# jack10_breakout.net
KiCad netlist of a schematic drawn in EAGLE
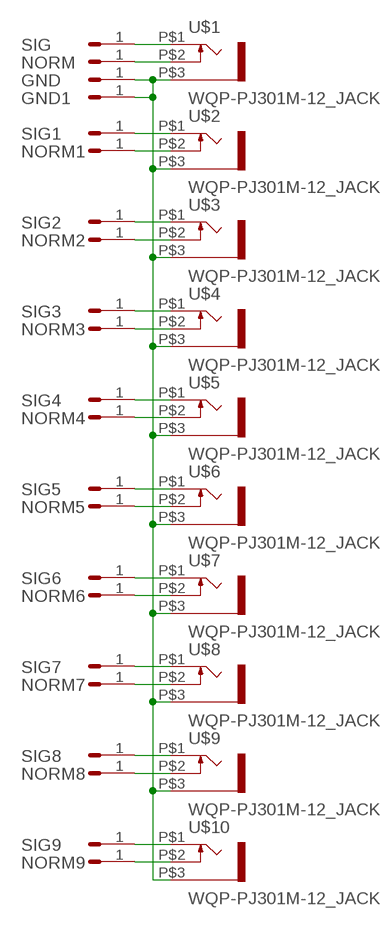
[diagram p0: schematic, sheet 1]

(export (version "E")
  (design (tool "Eeschema 10.0.6"))
  (components
    (comp (ref "GND")
      (value "HEADER/MALE/01")
      (footprint "eagle-import:HEADER_MALE_01")
      (libsource (lib "eagle-import") (part "HEADER/MALE/01"))
    )
    (comp (ref "GND1")
      (value "HEADER/MALE/01")
      (footprint "eagle-import:HEADER_MALE_01")
      (libsource (lib "eagle-import") (part "HEADER/MALE/01"))
    )
    (comp (ref "NORM")
      (value "HEADER/MALE/01")
      (footprint "eagle-import:HEADER_MALE_01")
      (libsource (lib "eagle-import") (part "HEADER/MALE/01"))
    )
    (comp (ref "NORM1")
      (value "HEADER/MALE/01")
      (footprint "eagle-import:HEADER_MALE_01")
      (libsource (lib "eagle-import") (part "HEADER/MALE/01"))
    )
    (comp (ref "NORM2")
      (value "HEADER/MALE/01")
      (footprint "eagle-import:HEADER_MALE_01")
      (libsource (lib "eagle-import") (part "HEADER/MALE/01"))
    )
    (comp (ref "NORM3")
      (value "HEADER/MALE/01")
      (footprint "eagle-import:HEADER_MALE_01")
      (libsource (lib "eagle-import") (part "HEADER/MALE/01"))
    )
    (comp (ref "NORM4")
      (value "HEADER/MALE/01")
      (footprint "eagle-import:HEADER_MALE_01")
      (libsource (lib "eagle-import") (part "HEADER/MALE/01"))
    )
    (comp (ref "NORM5")
      (value "HEADER/MALE/01")
      (footprint "eagle-import:HEADER_MALE_01")
      (libsource (lib "eagle-import") (part "HEADER/MALE/01"))
    )
    (comp (ref "NORM6")
      (value "HEADER/MALE/01")
      (footprint "eagle-import:HEADER_MALE_01")
      (libsource (lib "eagle-import") (part "HEADER/MALE/01"))
    )
    (comp (ref "NORM7")
      (value "HEADER/MALE/01")
      (footprint "eagle-import:HEADER_MALE_01")
      (libsource (lib "eagle-import") (part "HEADER/MALE/01"))
    )
    (comp (ref "NORM8")
      (value "HEADER/MALE/01")
      (footprint "eagle-import:HEADER_MALE_01")
      (libsource (lib "eagle-import") (part "HEADER/MALE/01"))
    )
    (comp (ref "NORM9")
      (value "HEADER/MALE/01")
      (footprint "eagle-import:HEADER_MALE_01")
      (libsource (lib "eagle-import") (part "HEADER/MALE/01"))
    )
    (comp (ref "SIG")
      (value "HEADER/MALE/01")
      (footprint "eagle-import:HEADER_MALE_01")
      (libsource (lib "eagle-import") (part "HEADER/MALE/01"))
    )
    (comp (ref "SIG1")
      (value "HEADER/MALE/01")
      (footprint "eagle-import:HEADER_MALE_01")
      (libsource (lib "eagle-import") (part "HEADER/MALE/01"))
    )
    (comp (ref "SIG2")
      (value "HEADER/MALE/01")
      (footprint "eagle-import:HEADER_MALE_01")
      (libsource (lib "eagle-import") (part "HEADER/MALE/01"))
    )
    (comp (ref "SIG3")
      (value "HEADER/MALE/01")
      (footprint "eagle-import:HEADER_MALE_01")
      (libsource (lib "eagle-import") (part "HEADER/MALE/01"))
    )
    (comp (ref "SIG4")
      (value "HEADER/MALE/01")
      (footprint "eagle-import:HEADER_MALE_01")
      (libsource (lib "eagle-import") (part "HEADER/MALE/01"))
    )
    (comp (ref "SIG5")
      (value "HEADER/MALE/01")
      (footprint "eagle-import:HEADER_MALE_01")
      (libsource (lib "eagle-import") (part "HEADER/MALE/01"))
    )
    (comp (ref "SIG6")
      (value "HEADER/MALE/01")
      (footprint "eagle-import:HEADER_MALE_01")
      (libsource (lib "eagle-import") (part "HEADER/MALE/01"))
    )
    (comp (ref "SIG7")
      (value "HEADER/MALE/01")
      (footprint "eagle-import:HEADER_MALE_01")
      (libsource (lib "eagle-import") (part "HEADER/MALE/01"))
    )
    (comp (ref "SIG8")
      (value "HEADER/MALE/01")
      (footprint "eagle-import:HEADER_MALE_01")
      (libsource (lib "eagle-import") (part "HEADER/MALE/01"))
    )
    (comp (ref "SIG9")
      (value "HEADER/MALE/01")
      (footprint "eagle-import:HEADER_MALE_01")
      (libsource (lib "eagle-import") (part "HEADER/MALE/01"))
    )
    (comp (ref "U$1")
      (value "WQP-PJ301M-12_JACK")
      (footprint "eagle-import:WQP-PJ301M-12_JACK")
      (libsource (lib "eagle-import") (part "WQP-PJ301M-12_JACK"))
    )
    (comp (ref "U$2")
      (value "WQP-PJ301M-12_JACK")
      (footprint "eagle-import:WQP-PJ301M-12_JACK")
      (libsource (lib "eagle-import") (part "WQP-PJ301M-12_JACK"))
    )
    (comp (ref "U$3")
      (value "WQP-PJ301M-12_JACK")
      (footprint "eagle-import:WQP-PJ301M-12_JACK")
      (libsource (lib "eagle-import") (part "WQP-PJ301M-12_JACK"))
    )
    (comp (ref "U$4")
      (value "WQP-PJ301M-12_JACK")
      (footprint "eagle-import:WQP-PJ301M-12_JACK")
      (libsource (lib "eagle-import") (part "WQP-PJ301M-12_JACK"))
    )
    (comp (ref "U$5")
      (value "WQP-PJ301M-12_JACK")
      (footprint "eagle-import:WQP-PJ301M-12_JACK")
      (libsource (lib "eagle-import") (part "WQP-PJ301M-12_JACK"))
    )
    (comp (ref "U$6")
      (value "WQP-PJ301M-12_JACK")
      (footprint "eagle-import:WQP-PJ301M-12_JACK")
      (libsource (lib "eagle-import") (part "WQP-PJ301M-12_JACK"))
    )
    (comp (ref "U$7")
      (value "WQP-PJ301M-12_JACK")
      (footprint "eagle-import:WQP-PJ301M-12_JACK")
      (libsource (lib "eagle-import") (part "WQP-PJ301M-12_JACK"))
    )
    (comp (ref "U$8")
      (value "WQP-PJ301M-12_JACK")
      (footprint "eagle-import:WQP-PJ301M-12_JACK")
      (libsource (lib "eagle-import") (part "WQP-PJ301M-12_JACK"))
    )
    (comp (ref "U$9")
      (value "WQP-PJ301M-12_JACK")
      (footprint "eagle-import:WQP-PJ301M-12_JACK")
      (libsource (lib "eagle-import") (part "WQP-PJ301M-12_JACK"))
    )
    (comp (ref "U$10")
      (value "WQP-PJ301M-12_JACK")
      (footprint "eagle-import:WQP-PJ301M-12_JACK")
      (libsource (lib "eagle-import") (part "WQP-PJ301M-12_JACK"))
    )
  )
  (nets
    (net (code "1") (name "Net-(GND-3)") (class "Default")
      (node (ref "GND") (pin "1") (pinfunction "3_1") (pintype "passive"))
      (node (ref "GND1") (pin "1") (pinfunction "3_1") (pintype "passive"))
      (node (ref "U$1") (pin "P$3") (pinfunction "1_P$3") (pintype "passive"))
      (node (ref "U$10") (pin "P$3") (pinfunction "1_P$3") (pintype "passive"))
      (node (ref "U$2") (pin "P$3") (pinfunction "1_P$3") (pintype "passive"))
      (node (ref "U$3") (pin "P$3") (pinfunction "1_P$3") (pintype "passive"))
      (node (ref "U$4") (pin "P$3") (pinfunction "1_P$3") (pintype "passive"))
      (node (ref "U$5") (pin "P$3") (pinfunction "1_P$3") (pintype "passive"))
      (node (ref "U$6") (pin "P$3") (pinfunction "1_P$3") (pintype "passive"))
      (node (ref "U$7") (pin "P$3") (pinfunction "1_P$3") (pintype "passive"))
      (node (ref "U$8") (pin "P$3") (pinfunction "1_P$3") (pintype "passive"))
      (node (ref "U$9") (pin "P$3") (pinfunction "1_P$3") (pintype "passive"))
    )
    (net (code "2") (name "Net-(NORM-3)") (class "Default")
      (node (ref "NORM") (pin "1") (pinfunction "3_1") (pintype "passive"))
      (node (ref "U$1") (pin "P$2") (pinfunction "3_P$2") (pintype "passive"))
    )
    (net (code "3") (name "Net-(NORM1-3)") (class "Default")
      (node (ref "NORM1") (pin "1") (pinfunction "3_1") (pintype "passive"))
      (node (ref "U$2") (pin "P$2") (pinfunction "3_P$2") (pintype "passive"))
    )
    (net (code "4") (name "Net-(NORM2-3)") (class "Default")
      (node (ref "NORM2") (pin "1") (pinfunction "3_1") (pintype "passive"))
      (node (ref "U$3") (pin "P$2") (pinfunction "3_P$2") (pintype "passive"))
    )
    (net (code "5") (name "Net-(NORM3-3)") (class "Default")
      (node (ref "NORM3") (pin "1") (pinfunction "3_1") (pintype "passive"))
      (node (ref "U$4") (pin "P$2") (pinfunction "3_P$2") (pintype "passive"))
    )
    (net (code "6") (name "Net-(NORM4-3)") (class "Default")
      (node (ref "NORM4") (pin "1") (pinfunction "3_1") (pintype "passive"))
      (node (ref "U$5") (pin "P$2") (pinfunction "3_P$2") (pintype "passive"))
    )
    (net (code "7") (name "Net-(NORM5-3)") (class "Default")
      (node (ref "NORM5") (pin "1") (pinfunction "3_1") (pintype "passive"))
      (node (ref "U$6") (pin "P$2") (pinfunction "3_P$2") (pintype "passive"))
    )
    (net (code "8") (name "Net-(NORM6-3)") (class "Default")
      (node (ref "NORM6") (pin "1") (pinfunction "3_1") (pintype "passive"))
      (node (ref "U$7") (pin "P$2") (pinfunction "3_P$2") (pintype "passive"))
    )
    (net (code "9") (name "Net-(NORM7-3)") (class "Default")
      (node (ref "NORM7") (pin "1") (pinfunction "3_1") (pintype "passive"))
      (node (ref "U$8") (pin "P$2") (pinfunction "3_P$2") (pintype "passive"))
    )
    (net (code "10") (name "Net-(NORM8-3)") (class "Default")
      (node (ref "NORM8") (pin "1") (pinfunction "3_1") (pintype "passive"))
      (node (ref "U$9") (pin "P$2") (pinfunction "3_P$2") (pintype "passive"))
    )
    (net (code "11") (name "Net-(NORM9-3)") (class "Default")
      (node (ref "NORM9") (pin "1") (pinfunction "3_1") (pintype "passive"))
      (node (ref "U$10") (pin "P$2") (pinfunction "3_P$2") (pintype "passive"))
    )
    (net (code "12") (name "Net-(SIG-3)") (class "Default")
      (node (ref "SIG") (pin "1") (pinfunction "3_1") (pintype "passive"))
      (node (ref "U$1") (pin "P$1") (pinfunction "2_P$1") (pintype "passive"))
    )
    (net (code "13") (name "Net-(SIG1-3)") (class "Default")
      (node (ref "SIG1") (pin "1") (pinfunction "3_1") (pintype "passive"))
      (node (ref "U$2") (pin "P$1") (pinfunction "2_P$1") (pintype "passive"))
    )
    (net (code "14") (name "Net-(SIG2-3)") (class "Default")
      (node (ref "SIG2") (pin "1") (pinfunction "3_1") (pintype "passive"))
      (node (ref "U$3") (pin "P$1") (pinfunction "2_P$1") (pintype "passive"))
    )
    (net (code "15") (name "Net-(SIG3-3)") (class "Default")
      (node (ref "SIG3") (pin "1") (pinfunction "3_1") (pintype "passive"))
      (node (ref "U$4") (pin "P$1") (pinfunction "2_P$1") (pintype "passive"))
    )
    (net (code "16") (name "Net-(SIG4-3)") (class "Default")
      (node (ref "SIG4") (pin "1") (pinfunction "3_1") (pintype "passive"))
      (node (ref "U$5") (pin "P$1") (pinfunction "2_P$1") (pintype "passive"))
    )
    (net (code "17") (name "Net-(SIG5-3)") (class "Default")
      (node (ref "SIG5") (pin "1") (pinfunction "3_1") (pintype "passive"))
      (node (ref "U$6") (pin "P$1") (pinfunction "2_P$1") (pintype "passive"))
    )
    (net (code "18") (name "Net-(SIG6-3)") (class "Default")
      (node (ref "SIG6") (pin "1") (pinfunction "3_1") (pintype "passive"))
      (node (ref "U$7") (pin "P$1") (pinfunction "2_P$1") (pintype "passive"))
    )
    (net (code "19") (name "Net-(SIG7-3)") (class "Default")
      (node (ref "SIG7") (pin "1") (pinfunction "3_1") (pintype "passive"))
      (node (ref "U$8") (pin "P$1") (pinfunction "2_P$1") (pintype "passive"))
    )
    (net (code "20") (name "Net-(SIG8-3)") (class "Default")
      (node (ref "SIG8") (pin "1") (pinfunction "3_1") (pintype "passive"))
      (node (ref "U$9") (pin "P$1") (pinfunction "2_P$1") (pintype "passive"))
    )
    (net (code "21") (name "Net-(SIG9-3)") (class "Default")
      (node (ref "SIG9") (pin "1") (pinfunction "3_1") (pintype "passive"))
      (node (ref "U$10") (pin "P$1") (pinfunction "2_P$1") (pintype "passive"))
    )
  )
)
